# tive-c-dev-shield.net
KiCad netlist of a schematic drawn in EAGLE
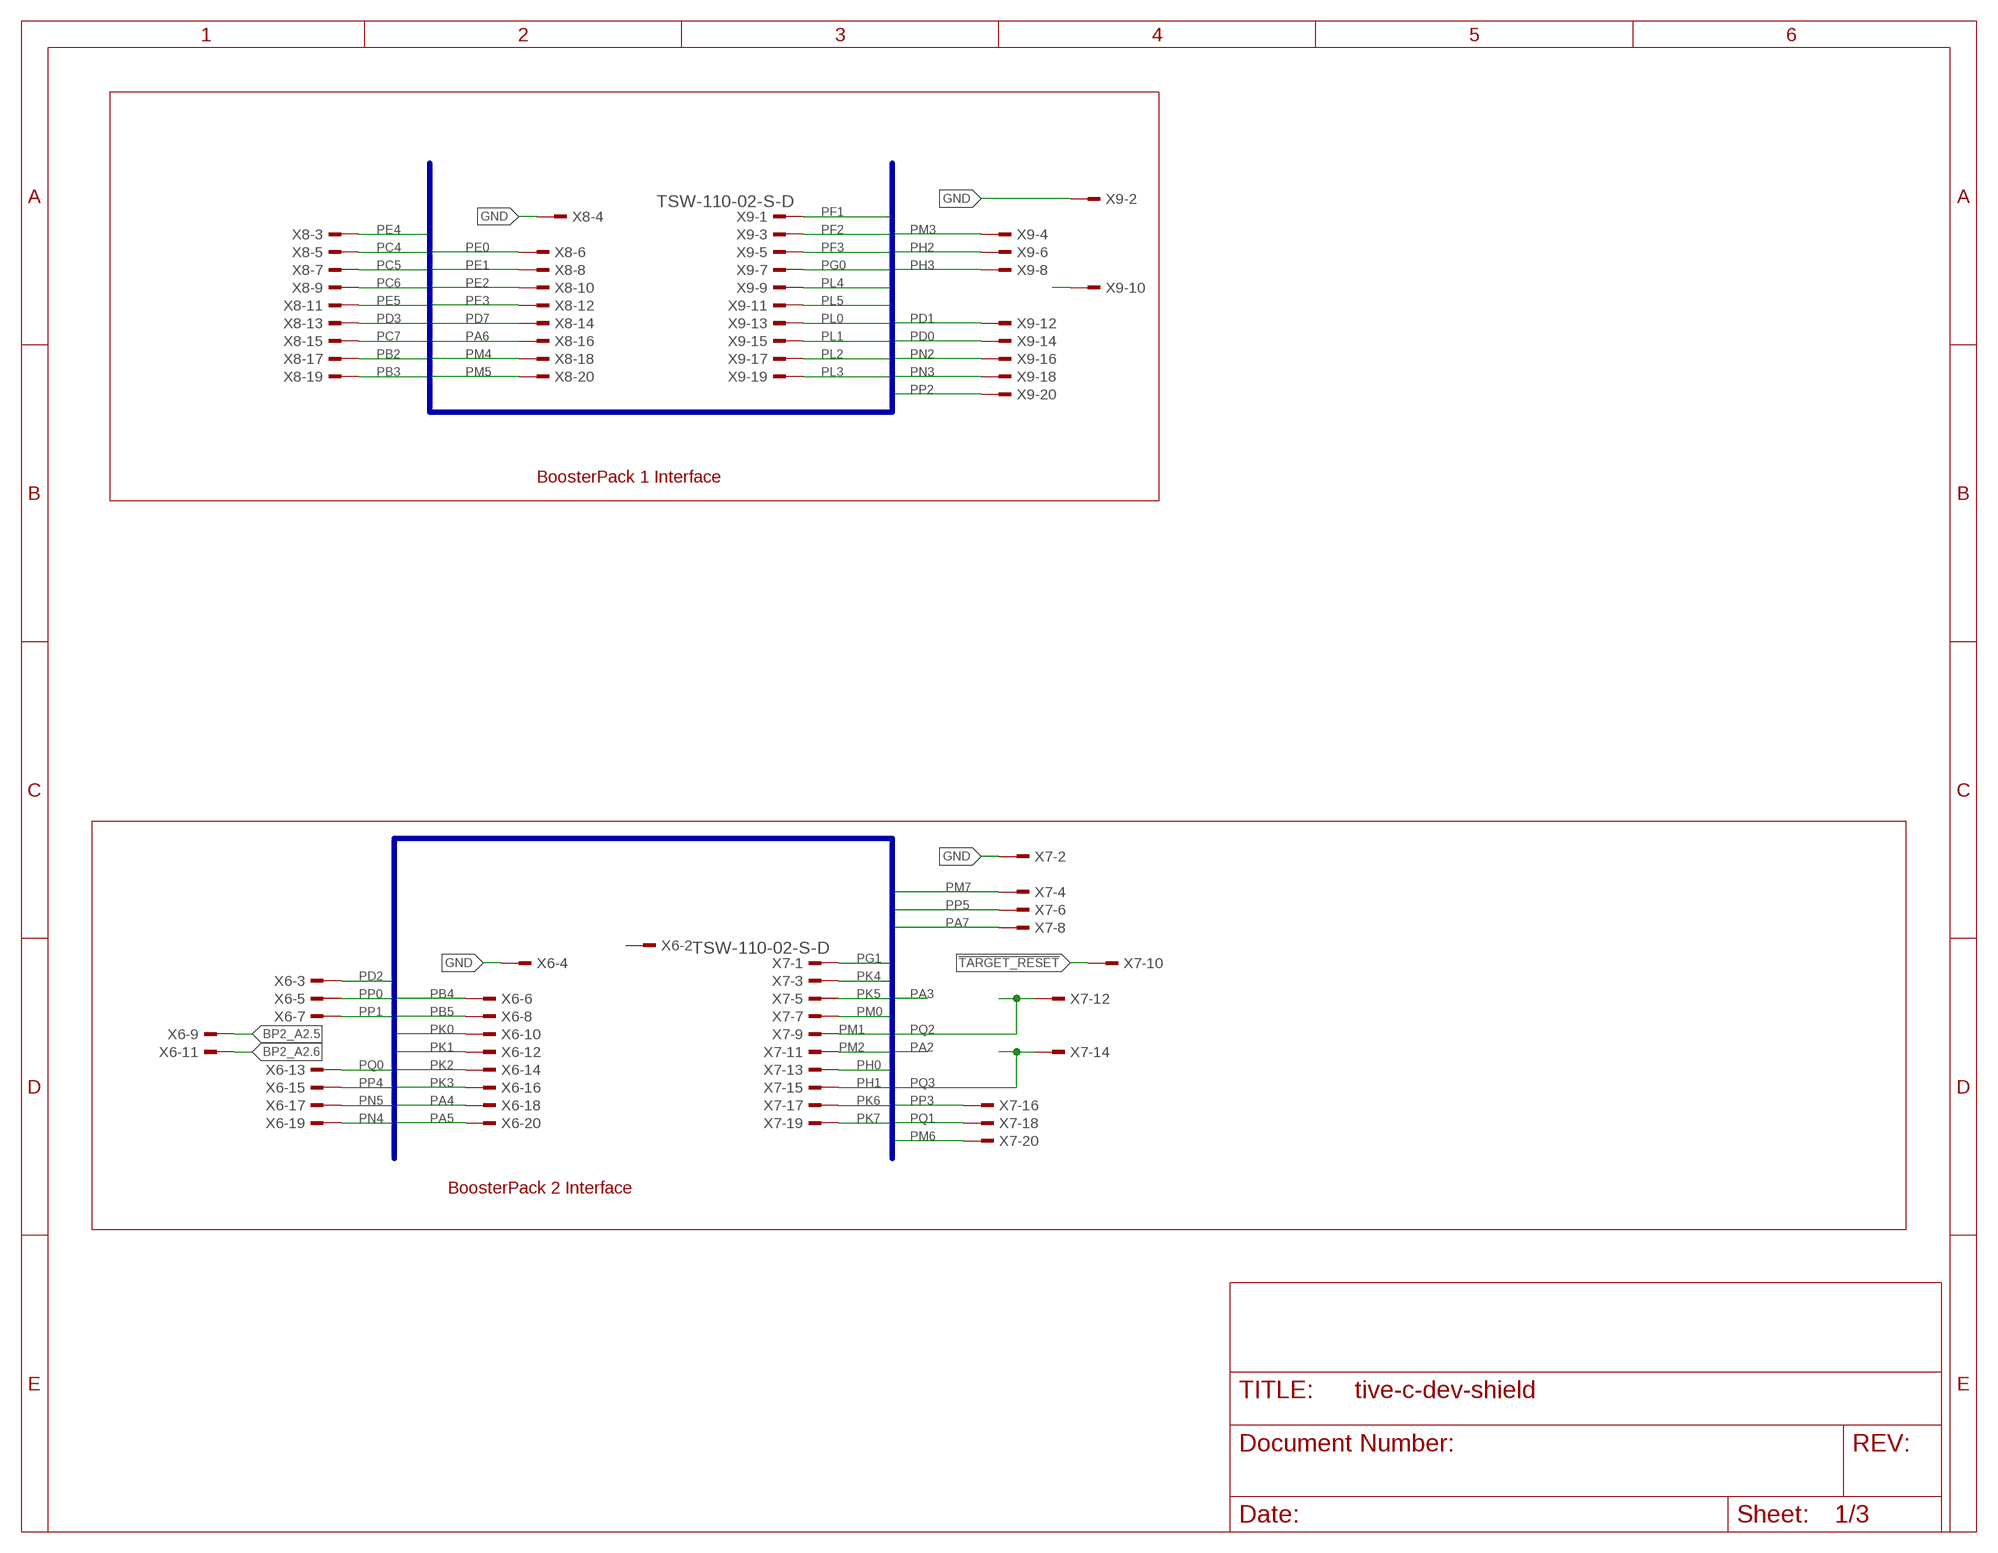
[diagram p0: schematic, sheet 1]
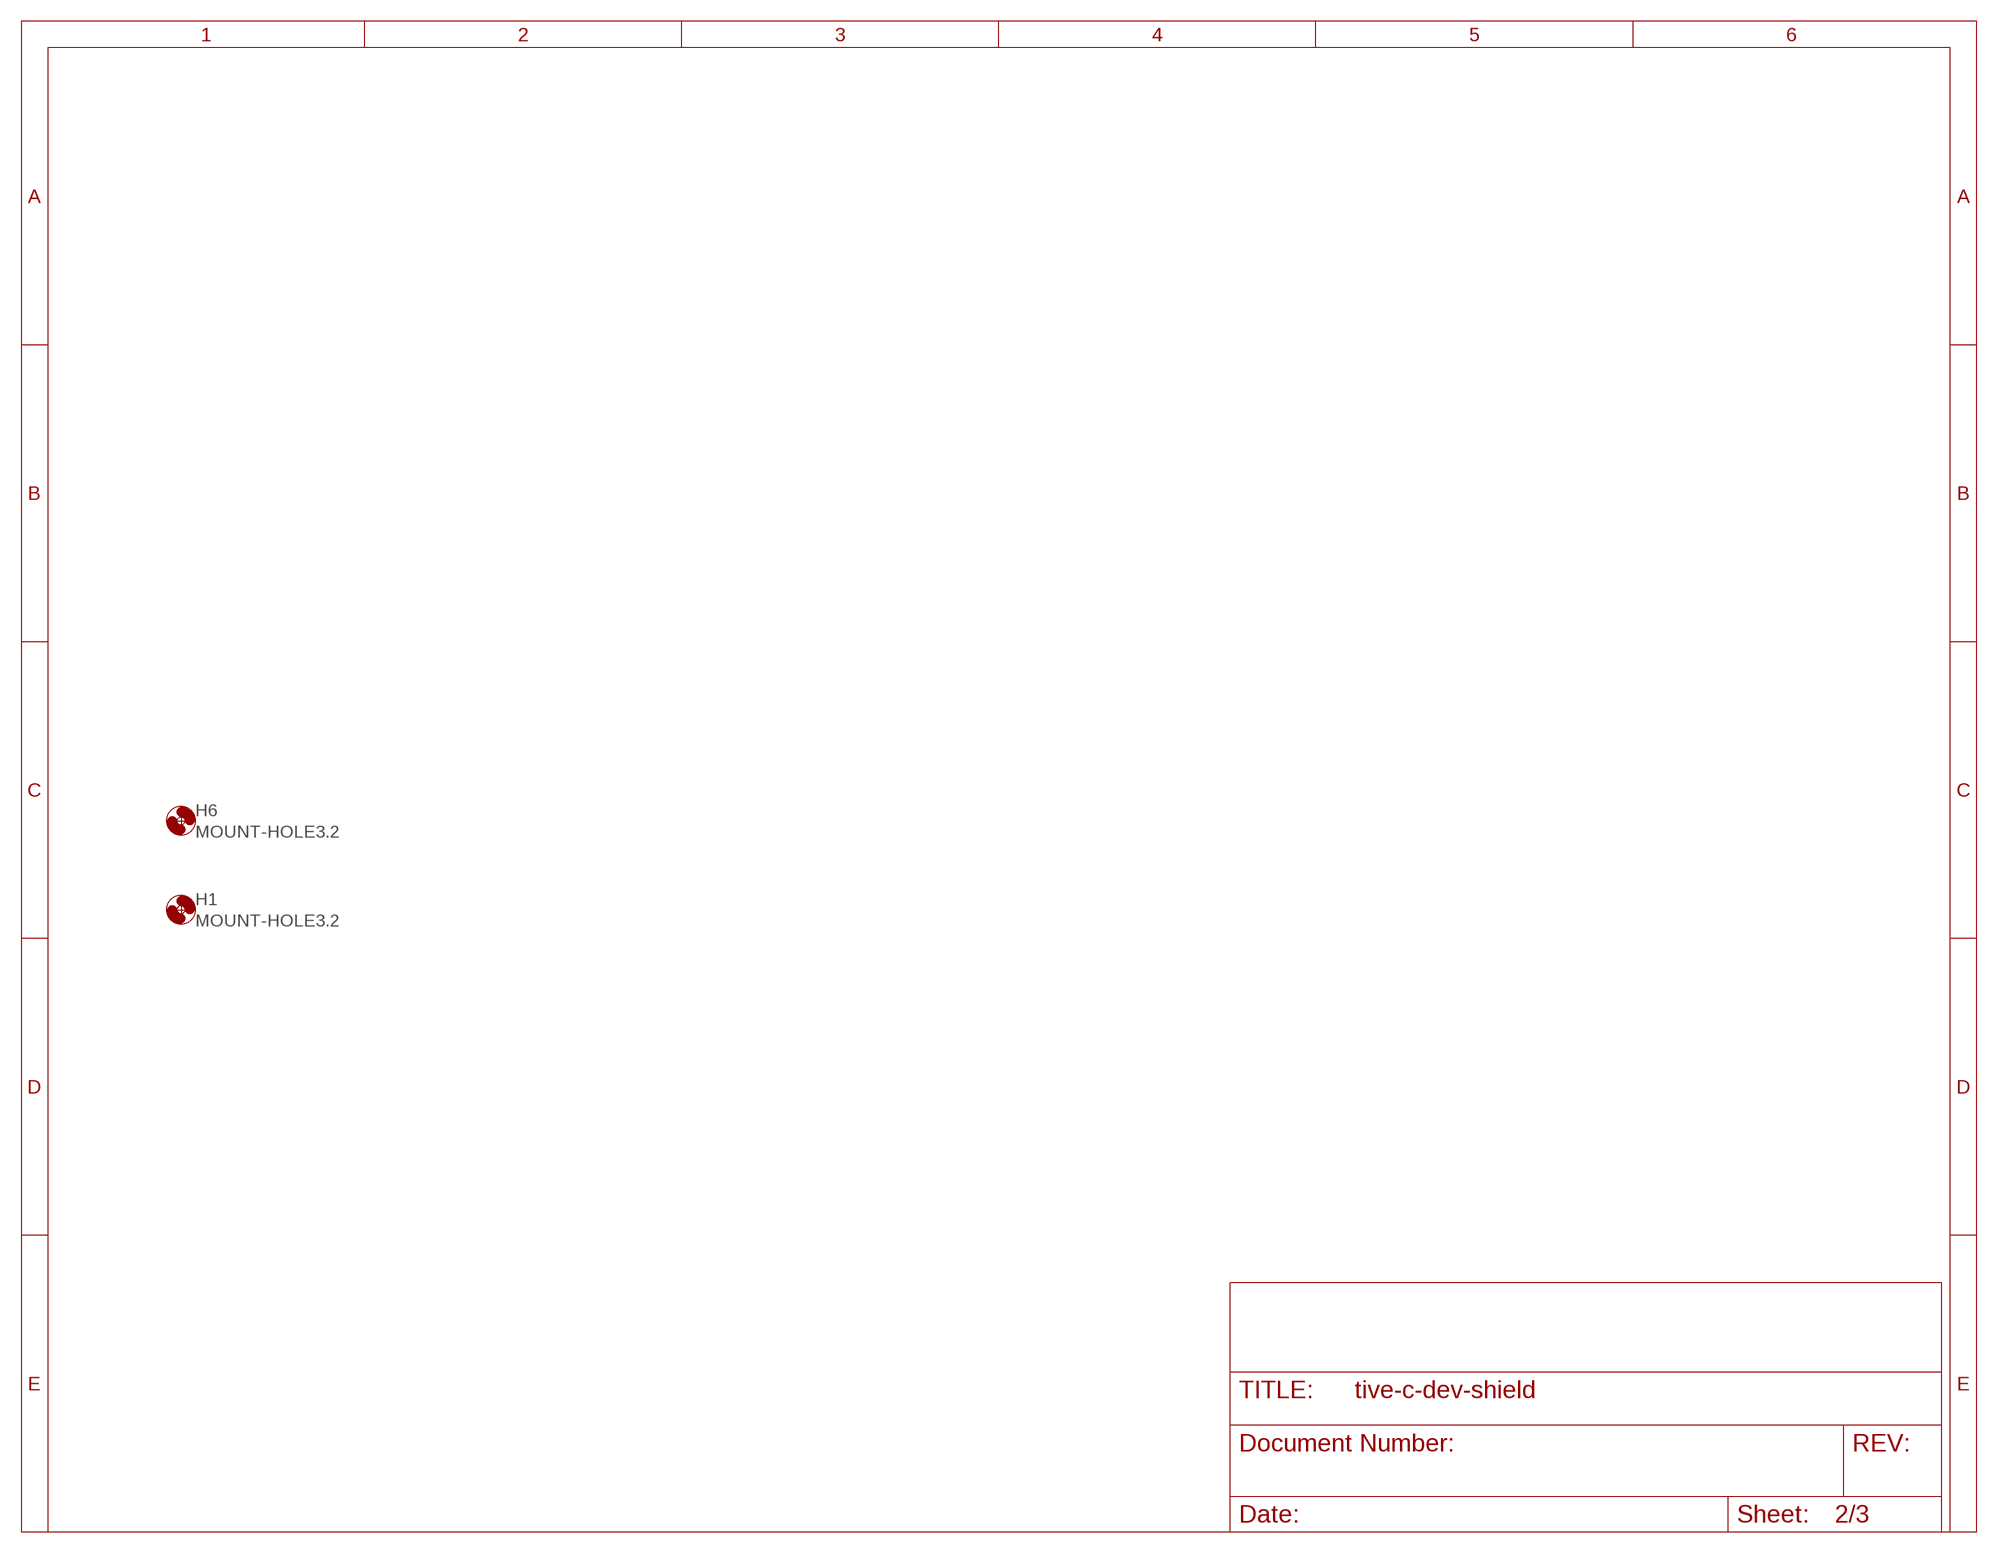
[diagram p1: schematic, sheet 2]
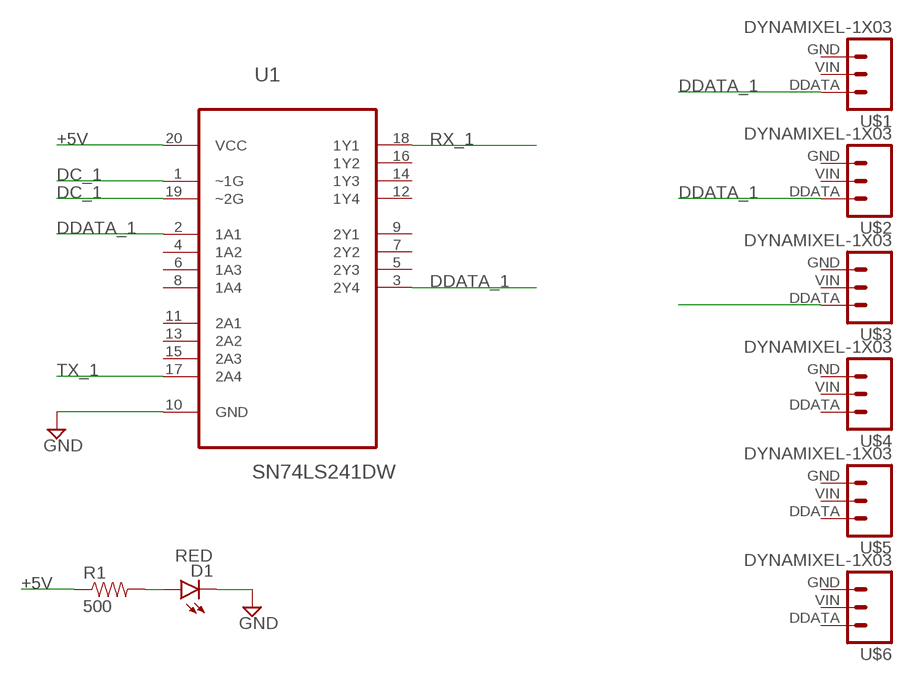
[diagram p2: schematic, sheet 3]

(export (version "E")
  (design (tool "Eeschema 10.0.6"))
  (components
    (comp (ref "D1")
      (value "RED")
      (footprint "eagle-import:LED-1206")
      (libsource (lib "eagle-import") (part "LED-RED1206"))
    )
    (comp (ref "R1")
      (value "500")
      (footprint "eagle-import:1206")
      (libsource (lib "eagle-import") (part "RESISTOR1206"))
    )
    (comp (ref "U$1")
      (value "DYNAMIXEL-1X03")
      (footprint "eagle-import:DYNAMIXEL-1X03")
      (libsource (lib "eagle-import") (part "DYNAMIXEL-1X03"))
    )
    (comp (ref "U$2")
      (value "DYNAMIXEL-1X03")
      (footprint "eagle-import:DYNAMIXEL-1X03")
      (libsource (lib "eagle-import") (part "DYNAMIXEL-1X03"))
    )
    (comp (ref "U$3")
      (value "DYNAMIXEL-1X03")
      (footprint "eagle-import:DYNAMIXEL-1X03")
      (libsource (lib "eagle-import") (part "DYNAMIXEL-1X03"))
    )
    (comp (ref "U$4")
      (value "DYNAMIXEL-1X03")
      (footprint "eagle-import:DYNAMIXEL-1X03")
      (libsource (lib "eagle-import") (part "DYNAMIXEL-1X03"))
    )
    (comp (ref "U$5")
      (value "DYNAMIXEL-1X03")
      (footprint "eagle-import:DYNAMIXEL-1X03")
      (libsource (lib "eagle-import") (part "DYNAMIXEL-1X03"))
    )
    (comp (ref "U$6")
      (value "DYNAMIXEL-1X03")
      (footprint "eagle-import:DYNAMIXEL-1X03")
      (libsource (lib "eagle-import") (part "DYNAMIXEL-1X03"))
    )
    (comp (ref "U1")
      (value "SN74LS241DW")
      (footprint "eagle-import:SOIC127P1030X265-20N")
      (libsource (lib "eagle-import") (part "SN74LS241DW"))
    )
    (comp (ref "X6")
      (value "TSW-110-02-S-D")
      (footprint "eagle-import:TSW-110-02-S-D")
      (fields (field (name "GNUM") "G22-THSTK-2X10-BAC"))
      (libsource (lib "eagle-import") (part "TSW-110-02-S-D"))
    )
    (comp (ref "X7")
      (value "TSW-110-02-S-D")
      (footprint "eagle-import:TSW-110-02-S-D")
      (fields (field (name "GNUM") "G22-THSTK-2X10-BAC"))
      (libsource (lib "eagle-import") (part "TSW-110-02-S-D"))
    )
    (comp (ref "X8")
      (value "TSW-110-02-S-D")
      (footprint "eagle-import:TSW-110-02-S-D")
      (fields (field (name "GNUM") "G22-THSTK-2X10-BAC"))
      (libsource (lib "eagle-import") (part "TSW-110-02-S-D"))
    )
    (comp (ref "X9")
      (value "TSW-110-02-S-D")
      (footprint "eagle-import:TSW-110-02-S-D")
      (fields (field (name "GNUM") "G22-THSTK-2X10-BAC"))
      (libsource (lib "eagle-import") (part "TSW-110-02-S-D"))
    )
    (comp (ref "H1")
      (value "MOUNT-HOLE3.2")
      (footprint "eagle-import:3,2")
      (libsource (lib "eagle-import") (part "MOUNT-HOLE3.2"))
    )
    (comp (ref "H6")
      (value "MOUNT-HOLE3.2")
      (footprint "eagle-import:3,2")
      (libsource (lib "eagle-import") (part "MOUNT-HOLE3.2"))
    )
  )
  (nets
    (net (code "1") (name "+5V") (class "Default")
      (node (ref "R1") (pin "1") (pinfunction "1_1") (pintype "passive"))
      (node (ref "U1") (pin "20") (pinfunction "VCC_20") (pintype "power_in"))
    )
    (net (code "2") (name "BP2_A2.5") (class "Default")
      (node (ref "X6") (pin "9") (pinfunction "1_9") (pintype "passive"))
    )
    (net (code "3") (name "BP2_A2.6") (class "Default")
      (node (ref "X6") (pin "11") (pinfunction "1_11") (pintype "passive"))
    )
    (net (code "4") (name "DC_1") (class "Default")
      (node (ref "U1") (pin "1") (pinfunction "~{1G}_1") (pintype "input"))
      (node (ref "U1") (pin "19") (pinfunction "~{2G}_19") (pintype "input"))
    )
    (net (code "5") (name "DDATA_1") (class "Default")
      (node (ref "U$1") (pin "DDATA") (pinfunction "3_DDATA") (pintype "passive"))
      (node (ref "U$2") (pin "DDATA") (pinfunction "3_DDATA") (pintype "passive"))
      (node (ref "U1") (pin "2") (pinfunction "1A1_2") (pintype "input"))
      (node (ref "U1") (pin "3") (pinfunction "2Y4_3") (pintype "output"))
    )
    (net (code "6") (name "GND") (class "Default")
      (node (ref "D1") (pin "C") (pinfunction "C_C") (pintype "passive"))
      (node (ref "U1") (pin "10") (pinfunction "GND_10") (pintype "passive"))
      (node (ref "X6") (pin "4") (pinfunction "1_4") (pintype "passive"))
      (node (ref "X7") (pin "2") (pinfunction "1_2") (pintype "passive"))
      (node (ref "X8") (pin "4") (pinfunction "1_4") (pintype "passive"))
      (node (ref "X9") (pin "2") (pinfunction "1_2") (pintype "passive"))
    )
    (net (code "7") (name "Net-(D1-PadA)") (class "Default")
      (node (ref "D1") (pin "A") (pinfunction "A_A") (pintype "passive"))
      (node (ref "R1") (pin "2") (pinfunction "2_2") (pintype "passive"))
    )
    (net (code "10") (name "PA4") (class "Default")
      (node (ref "X6") (pin "18") (pinfunction "1_18") (pintype "passive"))
    )
    (net (code "11") (name "PA5") (class "Default")
      (node (ref "X6") (pin "20") (pinfunction "1_20") (pintype "passive"))
    )
    (net (code "12") (name "PA6") (class "Default")
      (node (ref "X8") (pin "16") (pinfunction "1_16") (pintype "passive"))
    )
    (net (code "13") (name "PA7") (class "Default")
      (node (ref "X7") (pin "8") (pinfunction "1_8") (pintype "passive"))
    )
    (net (code "14") (name "PB2") (class "Default")
      (node (ref "X8") (pin "17") (pinfunction "1_17") (pintype "passive"))
    )
    (net (code "15") (name "PB3") (class "Default")
      (node (ref "X8") (pin "19") (pinfunction "1_19") (pintype "passive"))
    )
    (net (code "16") (name "PB4") (class "Default")
      (node (ref "X6") (pin "6") (pinfunction "1_6") (pintype "passive"))
    )
    (net (code "17") (name "PB5") (class "Default")
      (node (ref "X6") (pin "8") (pinfunction "1_8") (pintype "passive"))
    )
    (net (code "18") (name "PC4") (class "Default")
      (node (ref "X8") (pin "5") (pinfunction "1_5") (pintype "passive"))
    )
    (net (code "19") (name "PC5") (class "Default")
      (node (ref "X8") (pin "7") (pinfunction "1_7") (pintype "passive"))
    )
    (net (code "20") (name "PC6") (class "Default")
      (node (ref "X8") (pin "9") (pinfunction "1_9") (pintype "passive"))
    )
    (net (code "21") (name "PC7") (class "Default")
      (node (ref "X8") (pin "15") (pinfunction "1_15") (pintype "passive"))
    )
    (net (code "22") (name "PD0") (class "Default")
      (node (ref "X9") (pin "14") (pinfunction "1_14") (pintype "passive"))
    )
    (net (code "23") (name "PD1") (class "Default")
      (node (ref "X9") (pin "12") (pinfunction "1_12") (pintype "passive"))
    )
    (net (code "24") (name "PD2") (class "Default")
      (node (ref "X6") (pin "3") (pinfunction "1_3") (pintype "passive"))
    )
    (net (code "25") (name "PD3") (class "Default")
      (node (ref "X8") (pin "13") (pinfunction "1_13") (pintype "passive"))
    )
    (net (code "26") (name "PD7") (class "Default")
      (node (ref "X8") (pin "14") (pinfunction "1_14") (pintype "passive"))
    )
    (net (code "27") (name "PE0") (class "Default")
      (node (ref "X8") (pin "6") (pinfunction "1_6") (pintype "passive"))
    )
    (net (code "28") (name "PE1") (class "Default")
      (node (ref "X8") (pin "8") (pinfunction "1_8") (pintype "passive"))
    )
    (net (code "29") (name "PE2") (class "Default")
      (node (ref "X8") (pin "10") (pinfunction "1_10") (pintype "passive"))
    )
    (net (code "30") (name "PE3") (class "Default")
      (node (ref "X8") (pin "12") (pinfunction "1_12") (pintype "passive"))
    )
    (net (code "31") (name "PE4") (class "Default")
      (node (ref "X8") (pin "3") (pinfunction "1_3") (pintype "passive"))
    )
    (net (code "32") (name "PE5") (class "Default")
      (node (ref "X8") (pin "11") (pinfunction "1_11") (pintype "passive"))
    )
    (net (code "33") (name "PF1") (class "Default")
      (node (ref "X9") (pin "1") (pinfunction "1_1") (pintype "passive"))
    )
    (net (code "34") (name "PF2") (class "Default")
      (node (ref "X9") (pin "3") (pinfunction "1_3") (pintype "passive"))
    )
    (net (code "35") (name "PF3") (class "Default")
      (node (ref "X9") (pin "5") (pinfunction "1_5") (pintype "passive"))
    )
    (net (code "36") (name "PG0") (class "Default")
      (node (ref "X9") (pin "7") (pinfunction "1_7") (pintype "passive"))
    )
    (net (code "37") (name "PG1") (class "Default")
      (node (ref "X7") (pin "1") (pinfunction "1_1") (pintype "passive"))
    )
    (net (code "38") (name "PH0") (class "Default")
      (node (ref "X7") (pin "13") (pinfunction "1_13") (pintype "passive"))
    )
    (net (code "39") (name "PH1") (class "Default")
      (node (ref "X7") (pin "15") (pinfunction "1_15") (pintype "passive"))
    )
    (net (code "40") (name "PH2") (class "Default")
      (node (ref "X9") (pin "6") (pinfunction "1_6") (pintype "passive"))
    )
    (net (code "41") (name "PH3") (class "Default")
      (node (ref "X9") (pin "8") (pinfunction "1_8") (pintype "passive"))
    )
    (net (code "42") (name "PK0") (class "Default")
      (node (ref "X6") (pin "10") (pinfunction "1_10") (pintype "passive"))
    )
    (net (code "43") (name "PK1") (class "Default")
      (node (ref "X6") (pin "12") (pinfunction "1_12") (pintype "passive"))
    )
    (net (code "44") (name "PK2") (class "Default")
      (node (ref "X6") (pin "14") (pinfunction "1_14") (pintype "passive"))
    )
    (net (code "45") (name "PK3") (class "Default")
      (node (ref "X6") (pin "16") (pinfunction "1_16") (pintype "passive"))
    )
    (net (code "46") (name "PK4") (class "Default")
      (node (ref "X7") (pin "3") (pinfunction "1_3") (pintype "passive"))
    )
    (net (code "47") (name "PK5") (class "Default")
      (node (ref "X7") (pin "5") (pinfunction "1_5") (pintype "passive"))
    )
    (net (code "48") (name "PK6") (class "Default")
      (node (ref "X7") (pin "17") (pinfunction "1_17") (pintype "passive"))
    )
    (net (code "49") (name "PK7") (class "Default")
      (node (ref "X7") (pin "19") (pinfunction "1_19") (pintype "passive"))
    )
    (net (code "50") (name "PL0") (class "Default")
      (node (ref "X9") (pin "13") (pinfunction "1_13") (pintype "passive"))
    )
    (net (code "51") (name "PL1") (class "Default")
      (node (ref "X9") (pin "15") (pinfunction "1_15") (pintype "passive"))
    )
    (net (code "52") (name "PL2") (class "Default")
      (node (ref "X9") (pin "17") (pinfunction "1_17") (pintype "passive"))
    )
    (net (code "53") (name "PL3") (class "Default")
      (node (ref "X9") (pin "19") (pinfunction "1_19") (pintype "passive"))
    )
    (net (code "54") (name "PL4") (class "Default")
      (node (ref "X9") (pin "9") (pinfunction "1_9") (pintype "passive"))
    )
    (net (code "55") (name "PL5") (class "Default")
      (node (ref "X9") (pin "11") (pinfunction "1_11") (pintype "passive"))
    )
    (net (code "56") (name "PM0") (class "Default")
      (node (ref "X7") (pin "7") (pinfunction "1_7") (pintype "passive"))
    )
    (net (code "57") (name "PM1") (class "Default")
      (node (ref "X7") (pin "9") (pinfunction "1_9") (pintype "passive"))
    )
    (net (code "58") (name "PM2") (class "Default")
      (node (ref "X7") (pin "11") (pinfunction "1_11") (pintype "passive"))
    )
    (net (code "59") (name "PM3") (class "Default")
      (node (ref "X9") (pin "4") (pinfunction "1_4") (pintype "passive"))
    )
    (net (code "60") (name "PM4") (class "Default")
      (node (ref "X8") (pin "18") (pinfunction "1_18") (pintype "passive"))
    )
    (net (code "61") (name "PM5") (class "Default")
      (node (ref "X8") (pin "20") (pinfunction "1_20") (pintype "passive"))
    )
    (net (code "62") (name "PM6") (class "Default")
      (node (ref "X7") (pin "20") (pinfunction "1_20") (pintype "passive"))
    )
    (net (code "63") (name "PM7") (class "Default")
      (node (ref "X7") (pin "4") (pinfunction "1_4") (pintype "passive"))
    )
    (net (code "64") (name "PN2") (class "Default")
      (node (ref "X9") (pin "16") (pinfunction "1_16") (pintype "passive"))
    )
    (net (code "65") (name "PN3") (class "Default")
      (node (ref "X9") (pin "18") (pinfunction "1_18") (pintype "passive"))
    )
    (net (code "66") (name "PN4") (class "Default")
      (node (ref "X6") (pin "19") (pinfunction "1_19") (pintype "passive"))
    )
    (net (code "67") (name "PN5") (class "Default")
      (node (ref "X6") (pin "17") (pinfunction "1_17") (pintype "passive"))
    )
    (net (code "68") (name "PP0") (class "Default")
      (node (ref "X6") (pin "5") (pinfunction "1_5") (pintype "passive"))
    )
    (net (code "69") (name "PP1") (class "Default")
      (node (ref "X6") (pin "7") (pinfunction "1_7") (pintype "passive"))
    )
    (net (code "70") (name "PP2") (class "Default")
      (node (ref "X9") (pin "20") (pinfunction "1_20") (pintype "passive"))
    )
    (net (code "71") (name "PP3") (class "Default")
      (node (ref "X7") (pin "16") (pinfunction "1_16") (pintype "passive"))
    )
    (net (code "72") (name "PP4") (class "Default")
      (node (ref "X6") (pin "15") (pinfunction "1_15") (pintype "passive"))
    )
    (net (code "73") (name "PP5") (class "Default")
      (node (ref "X7") (pin "6") (pinfunction "1_6") (pintype "passive"))
    )
    (net (code "74") (name "PQ0") (class "Default")
      (node (ref "X6") (pin "13") (pinfunction "1_13") (pintype "passive"))
    )
    (net (code "75") (name "PQ1") (class "Default")
      (node (ref "X7") (pin "18") (pinfunction "1_18") (pintype "passive"))
    )
    (net (code "76") (name "PQ2") (class "Default")
      (node (ref "X7") (pin "12") (pinfunction "1_12") (pintype "passive"))
    )
    (net (code "77") (name "PQ3") (class "Default")
      (node (ref "X7") (pin "14") (pinfunction "1_14") (pintype "passive"))
    )
    (net (code "78") (name "RX_1") (class "Default")
      (node (ref "U1") (pin "18") (pinfunction "1Y1_18") (pintype "output"))
    )
    (net (code "79") (name "TX_1") (class "Default")
      (node (ref "U1") (pin "17") (pinfunction "2A4_17") (pintype "input"))
    )
    (net (code "80") (name "unconnected-(U$1-1-PadGND)") (class "Default")
      (node (ref "U$1") (pin "GND") (pinfunction "1_GND") (pintype "passive"))
    )
    (net (code "81") (name "unconnected-(U$1-2-PadVIN)") (class "Default")
      (node (ref "U$1") (pin "VIN") (pinfunction "2_VIN") (pintype "passive"))
    )
    (net (code "82") (name "unconnected-(U$2-1-PadGND)") (class "Default")
      (node (ref "U$2") (pin "GND") (pinfunction "1_GND") (pintype "passive"))
    )
    (net (code "83") (name "unconnected-(U$2-2-PadVIN)") (class "Default")
      (node (ref "U$2") (pin "VIN") (pinfunction "2_VIN") (pintype "passive"))
    )
    (net (code "84") (name "unconnected-(U$3-1-PadGND)") (class "Default")
      (node (ref "U$3") (pin "GND") (pinfunction "1_GND") (pintype "passive"))
    )
    (net (code "85") (name "unconnected-(U$3-2-PadVIN)") (class "Default")
      (node (ref "U$3") (pin "VIN") (pinfunction "2_VIN") (pintype "passive"))
    )
    (net (code "86") (name "unconnected-(U$3-3-PadDDATA)") (class "Default")
      (node (ref "U$3") (pin "DDATA") (pinfunction "3_DDATA") (pintype "passive"))
    )
    (net (code "87") (name "unconnected-(U$4-1-PadGND)") (class "Default")
      (node (ref "U$4") (pin "GND") (pinfunction "1_GND") (pintype "passive"))
    )
    (net (code "88") (name "unconnected-(U$4-2-PadVIN)") (class "Default")
      (node (ref "U$4") (pin "VIN") (pinfunction "2_VIN") (pintype "passive"))
    )
    (net (code "89") (name "unconnected-(U$4-3-PadDDATA)") (class "Default")
      (node (ref "U$4") (pin "DDATA") (pinfunction "3_DDATA") (pintype "passive"))
    )
    (net (code "90") (name "unconnected-(U$5-1-PadGND)") (class "Default")
      (node (ref "U$5") (pin "GND") (pinfunction "1_GND") (pintype "passive"))
    )
    (net (code "91") (name "unconnected-(U$5-2-PadVIN)") (class "Default")
      (node (ref "U$5") (pin "VIN") (pinfunction "2_VIN") (pintype "passive"))
    )
    (net (code "92") (name "unconnected-(U$5-3-PadDDATA)") (class "Default")
      (node (ref "U$5") (pin "DDATA") (pinfunction "3_DDATA") (pintype "passive"))
    )
    (net (code "93") (name "unconnected-(U$6-1-PadGND)") (class "Default")
      (node (ref "U$6") (pin "GND") (pinfunction "1_GND") (pintype "passive"))
    )
    (net (code "94") (name "unconnected-(U$6-2-PadVIN)") (class "Default")
      (node (ref "U$6") (pin "VIN") (pinfunction "2_VIN") (pintype "passive"))
    )
    (net (code "95") (name "unconnected-(U$6-3-PadDDATA)") (class "Default")
      (node (ref "U$6") (pin "DDATA") (pinfunction "3_DDATA") (pintype "passive"))
    )
    (net (code "96") (name "unconnected-(U1-1A2-Pad4)") (class "Default")
      (node (ref "U1") (pin "4") (pinfunction "1A2_4") (pintype "input"))
    )
    (net (code "97") (name "unconnected-(U1-1A3-Pad6)") (class "Default")
      (node (ref "U1") (pin "6") (pinfunction "1A3_6") (pintype "input"))
    )
    (net (code "98") (name "unconnected-(U1-1A4-Pad8)") (class "Default")
      (node (ref "U1") (pin "8") (pinfunction "1A4_8") (pintype "input"))
    )
    (net (code "99") (name "unconnected-(U1-1Y2-Pad16)") (class "Default")
      (node (ref "U1") (pin "16") (pinfunction "1Y2_16") (pintype "output"))
    )
    (net (code "100") (name "unconnected-(U1-1Y3-Pad14)") (class "Default")
      (node (ref "U1") (pin "14") (pinfunction "1Y3_14") (pintype "output"))
    )
    (net (code "101") (name "unconnected-(U1-1Y4-Pad12)") (class "Default")
      (node (ref "U1") (pin "12") (pinfunction "1Y4_12") (pintype "output"))
    )
    (net (code "102") (name "unconnected-(U1-2A1-Pad11)") (class "Default")
      (node (ref "U1") (pin "11") (pinfunction "2A1_11") (pintype "input"))
    )
    (net (code "103") (name "unconnected-(U1-2A2-Pad13)") (class "Default")
      (node (ref "U1") (pin "13") (pinfunction "2A2_13") (pintype "input"))
    )
    (net (code "104") (name "unconnected-(U1-2A3-Pad15)") (class "Default")
      (node (ref "U1") (pin "15") (pinfunction "2A3_15") (pintype "input"))
    )
    (net (code "105") (name "unconnected-(U1-2Y1-Pad9)") (class "Default")
      (node (ref "U1") (pin "9") (pinfunction "2Y1_9") (pintype "output"))
    )
    (net (code "106") (name "unconnected-(U1-2Y2-Pad7)") (class "Default")
      (node (ref "U1") (pin "7") (pinfunction "2Y2_7") (pintype "output"))
    )
    (net (code "107") (name "unconnected-(U1-2Y3-Pad5)") (class "Default")
      (node (ref "U1") (pin "5") (pinfunction "2Y3_5") (pintype "output"))
    )
    (net (code "108") (name "unconnected-(X6L-1-Pad2)") (class "Default")
      (node (ref "X6") (pin "2") (pinfunction "1_2") (pintype "passive"))
    )
    (net (code "109") (name "~{TARGET_RESET}") (class "Default")
      (node (ref "X7") (pin "10") (pinfunction "1_10") (pintype "passive"))
      (node (ref "X9") (pin "10") (pinfunction "1_10") (pintype "passive"))
    )
  )
)
